# boadr.net
KiCad netlist of a schematic drawn in Altium Designer
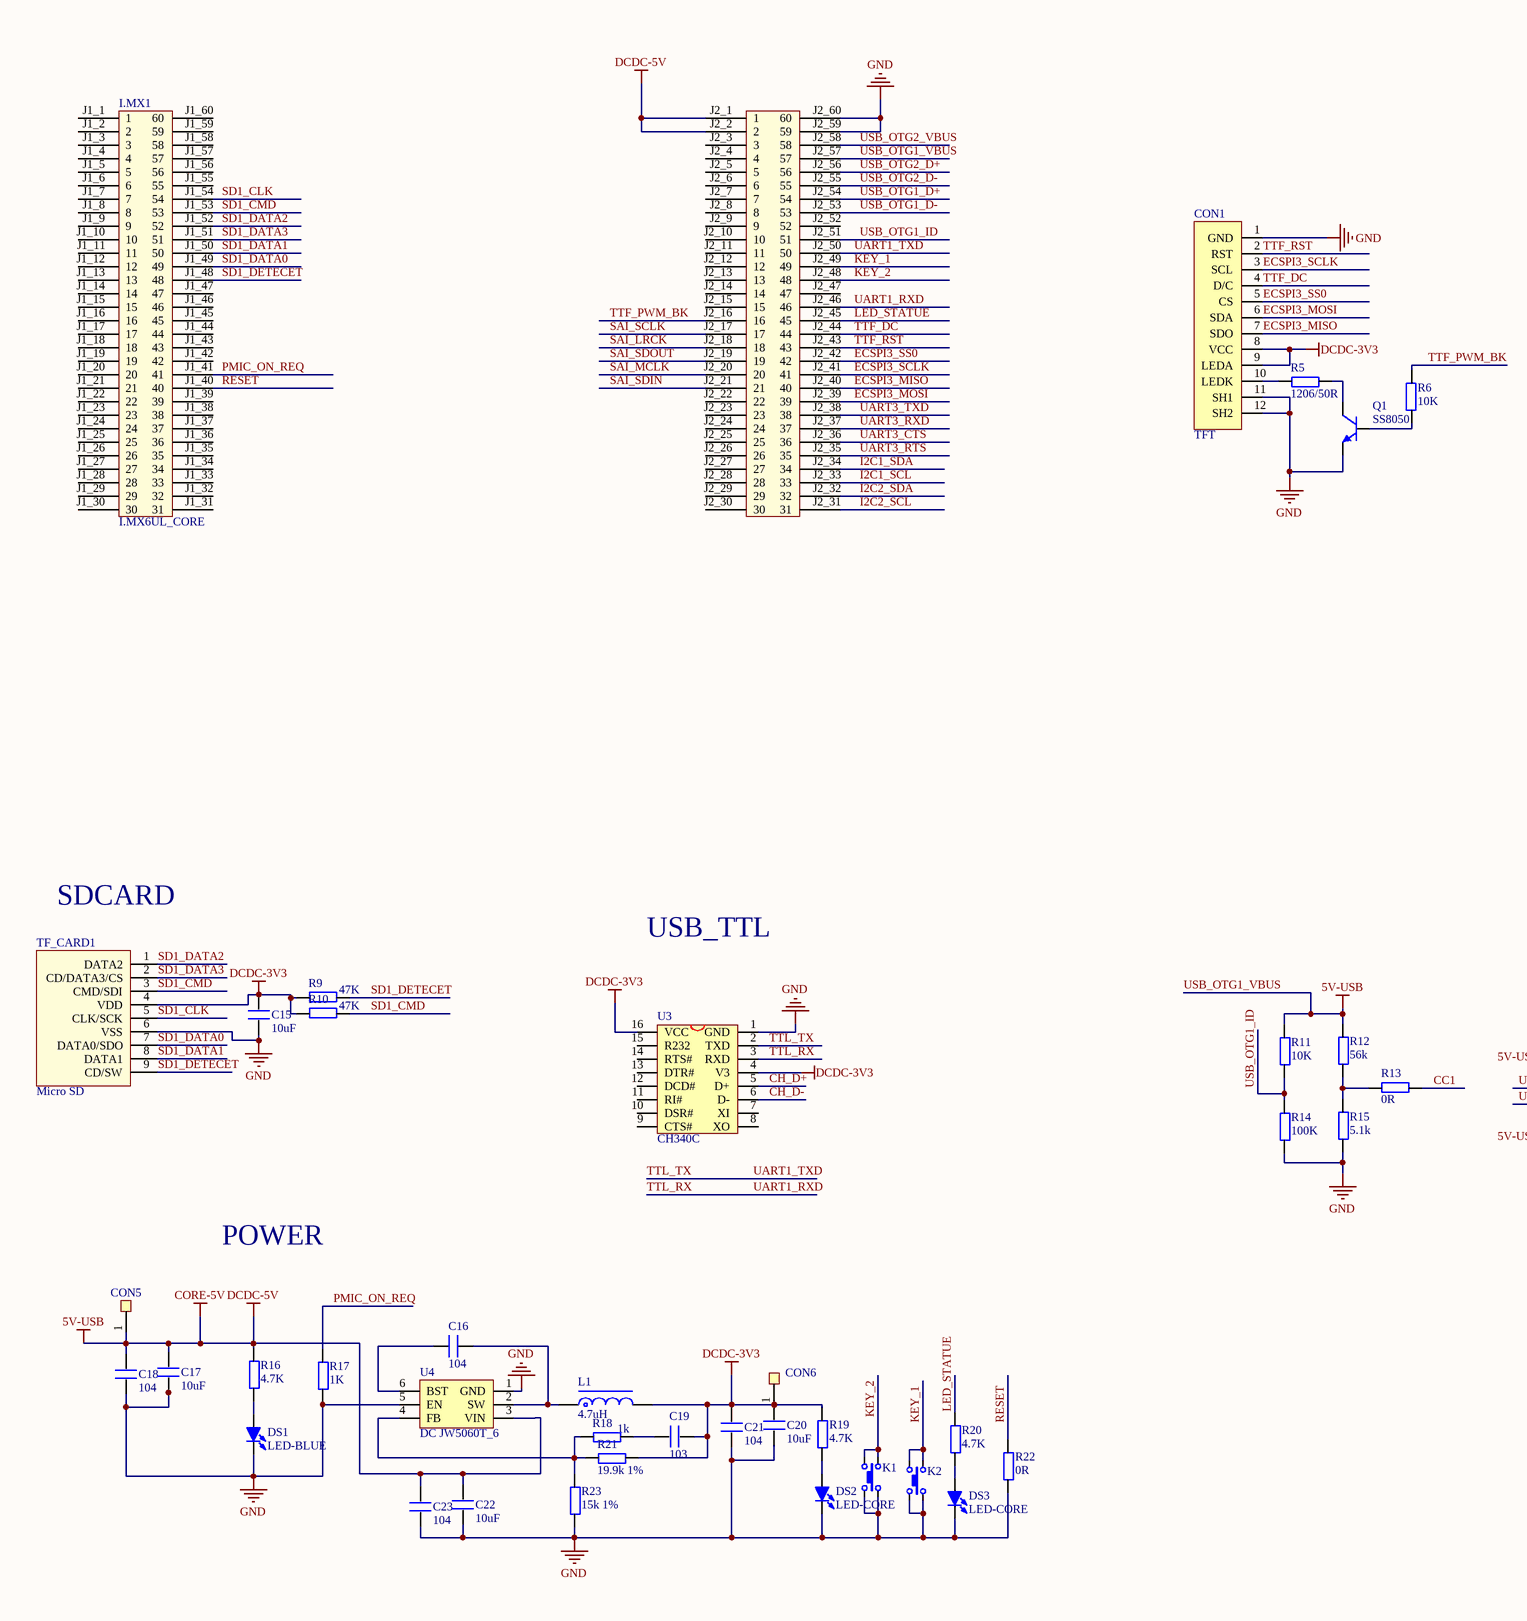
[diagram p0: boadr.SchDoc, left]
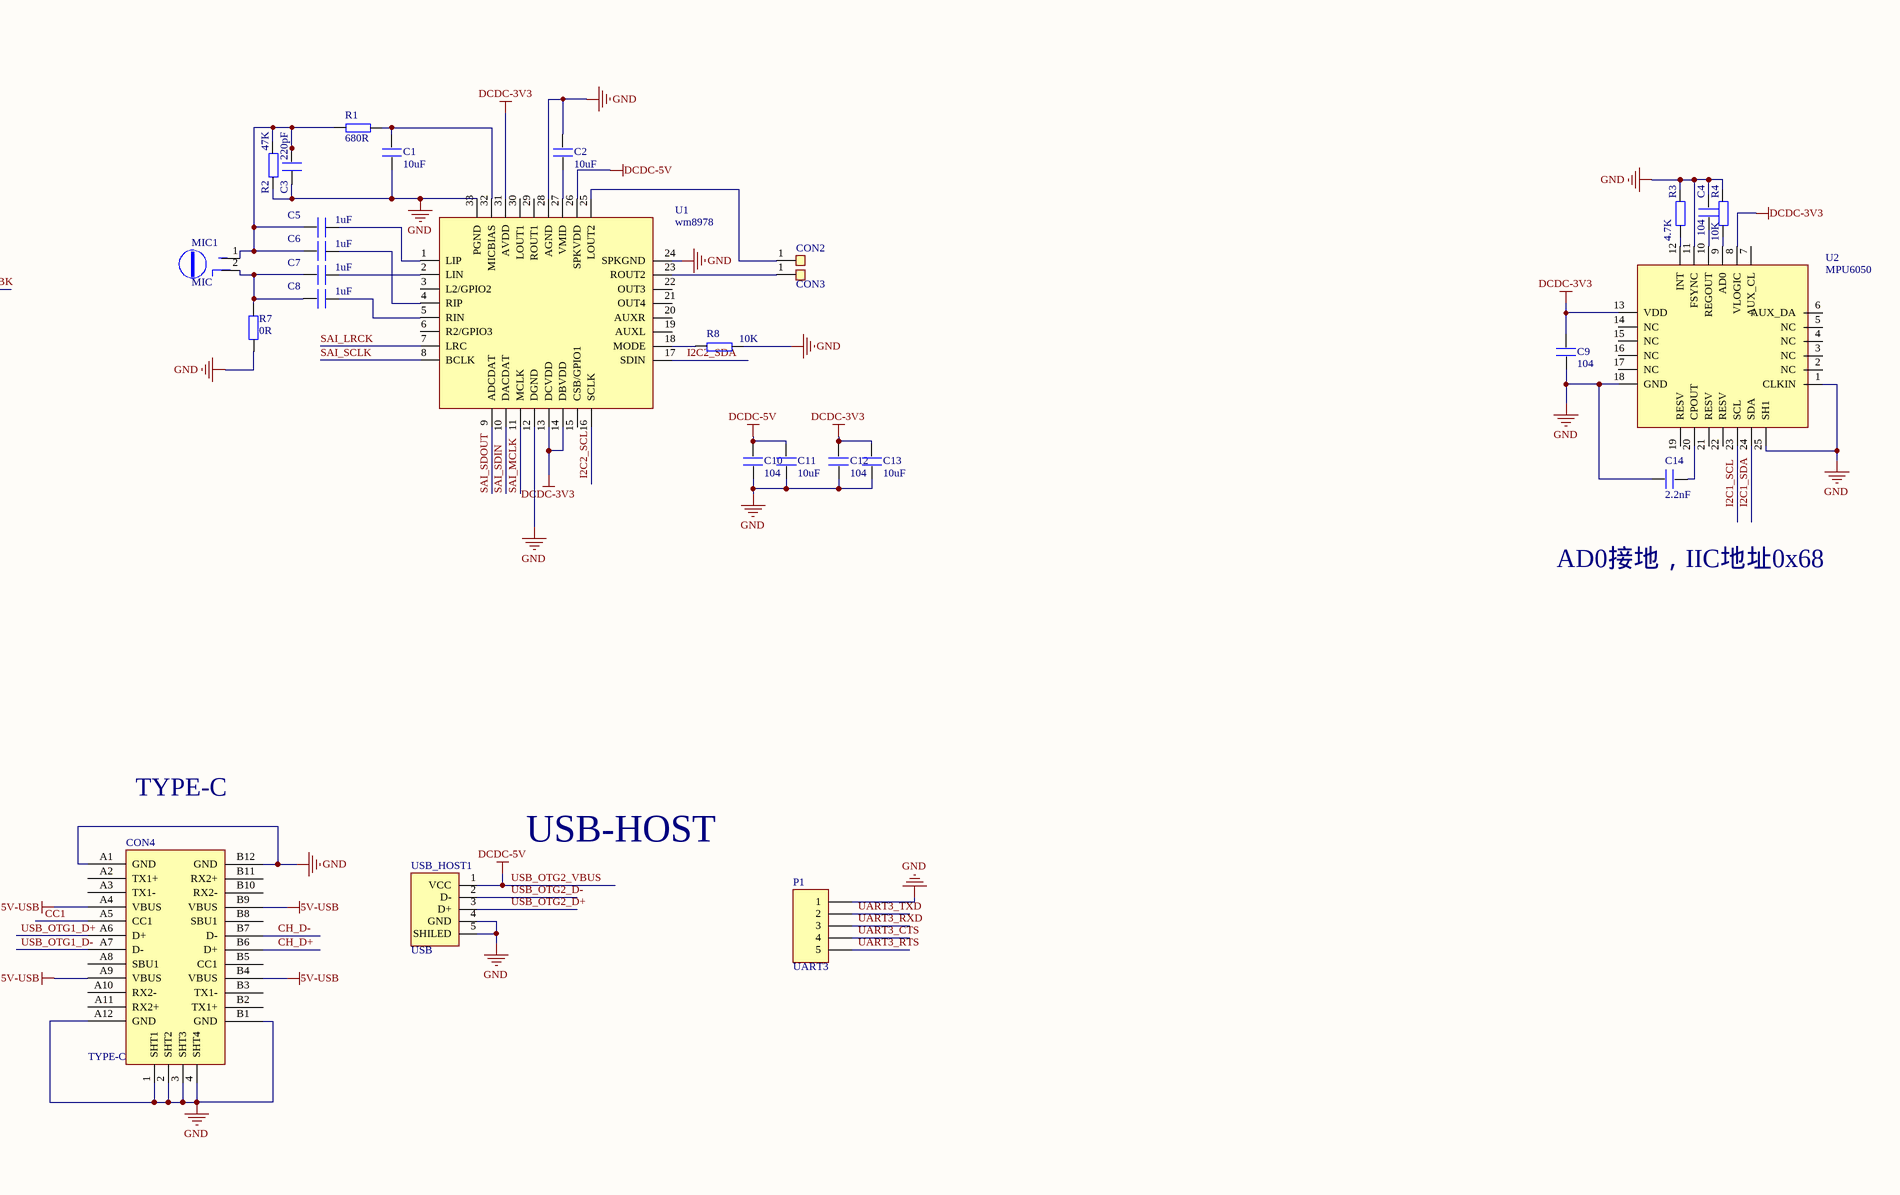
[diagram p1: boadr.SchDoc, right]

(export (version "E")
  (design (tool "Eeschema 10.0.6"))
  (components
    (comp (ref "C1") (value "10uF") (footprint "C 0603") (libsource (lib "IMX6UL_ALPHA(底板)_V2.0") (part "C")))
    (comp (ref "C2") (value "10uF") (footprint "C 0603") (libsource (lib "IMX6UL_ALPHA(底板)_V2.0") (part "C")))
    (comp (ref "C3")
      (value "220pF")
      (footprint "C 0603")
      (libsource (lib "IMX6UL_ALPHA(底板)_V2.0") (part "C"))
    )
    (comp (ref "C4") (value "104") (footprint "C 0603") (libsource (lib "IMX6UL_ALPHA(底板)_V2.0") (part "C")))
    (comp (ref "C5") (value "1uF") (footprint "C 0603") (libsource (lib "IMX6UL_ALPHA(底板)_V2.0") (part "C")))
    (comp (ref "C6") (value "1uF") (footprint "C 0603") (libsource (lib "IMX6UL_ALPHA(底板)_V2.0") (part "C")))
    (comp (ref "C7") (value "1uF") (footprint "C 0603") (libsource (lib "IMX6UL_ALPHA(底板)_V2.0") (part "C")))
    (comp (ref "C8") (value "1uF") (footprint "C 0603") (libsource (lib "IMX6UL_ALPHA(底板)_V2.0") (part "C")))
    (comp (ref "C9") (value "104") (footprint "C 0603") (libsource (lib "IMX6UL_ALPHA(底板)_V2.0") (part "C")))
    (comp (ref "C10") (value "104") (footprint "C 0603") (libsource (lib "IMX6UL_ALPHA(底板)_V2.0") (part "C")))
    (comp (ref "C11")
      (value "10uF")
      (footprint "C 0603")
      (libsource (lib "IMX6UL_ALPHA(底板)_V2.0") (part "C"))
    )
    (comp (ref "C12") (value "104") (footprint "C 0603") (libsource (lib "IMX6UL_ALPHA(底板)_V2.0") (part "C")))
    (comp (ref "C13")
      (value "10uF")
      (footprint "C 0603")
      (libsource (lib "IMX6UL_ALPHA(底板)_V2.0") (part "C"))
    )
    (comp (ref "C14")
      (value "2.2nF")
      (footprint "C 0603")
      (libsource (lib "IMX6UL_ALPHA(底板)_V2.0") (part "C"))
    )
    (comp (ref "C15")
      (value "10uF")
      (footprint "C 0603")
      (libsource (lib "IMX6UL_ALPHA(底板)_V2.0") (part "C"))
    )
    (comp (ref "C16") (value "104") (footprint "C 0603") (libsource (lib "IMX6UL_ALPHA(底板)_V2.0") (part "C")))
    (comp (ref "C17")
      (value "10uF")
      (footprint "C 0603")
      (libsource (lib "IMX6UL_ALPHA(底板)_V2.0") (part "C"))
    )
    (comp (ref "C18") (value "104") (footprint "C 0603") (libsource (lib "IMX6UL_ALPHA(底板)_V2.0") (part "C")))
    (comp (ref "C19") (value "103") (footprint "C 0603") (libsource (lib "IMX6UL_ALPHA(底板)_V2.0") (part "C")))
    (comp (ref "C20")
      (value "10uF")
      (footprint "C 0603")
      (libsource (lib "IMX6UL_ALPHA(底板)_V2.0") (part "C"))
    )
    (comp (ref "C21") (value "104") (footprint "C 0603") (libsource (lib "IMX6UL_ALPHA(底板)_V2.0") (part "C")))
    (comp (ref "C22")
      (value "10uF")
      (footprint "C 0603")
      (libsource (lib "IMX6UL_ALPHA(底板)_V2.0") (part "C"))
    )
    (comp (ref "C23") (value "104") (footprint "C 0603") (libsource (lib "IMX6UL_ALPHA(底板)_V2.0") (part "C")))
    (comp (ref "CON1")
      (value "TFT")
      (footprint "FPC连接器")
      (libsource (lib "Schlib_cloudy") (part "TFT_SPI_10PIN"))
    )
    (comp (ref "CON2") (value "connector") (footprint "PIN-1-TEST") (libsource (lib "") (part "PIN-1_1")))
    (comp (ref "CON3") (value "connector") (footprint "PIN-1-TEST") (libsource (lib "") (part "PIN-1_1")))
    (comp (ref "CON4")
      (value "TYPE-C")
      (footprint "type-c")
      (libsource (lib "Schlib_cloudy") (part "TYPE-C"))
    )
    (comp (ref "CON5")
      (value "connector")
      (footprint "PIN-1-TEST")
      (libsource (lib "Schlib_cloudy") (part "PIN-1"))
    )
    (comp (ref "CON6")
      (value "connector")
      (footprint "PIN-1-TEST")
      (libsource (lib "Schlib_cloudy") (part "PIN-1"))
    )
    (comp (ref "DS1")
      (value "LED-BLUE")
      (footprint "LED-0603")
      (description "贴片LED")
      (fields (field (name "版权归属") "源创客"))
      (libsource (lib "IMX6UL_ALPHA(底板)_V2.0") (part "LED-SMD"))
    )
    (comp (ref "DS2")
      (value "LED-CORE")
      (footprint "LED 0603R")
      (description "贴片LED")
      (fields (field (name "版权归属") "源创客"))
      (libsource (lib "IMX6UL_ALPHA(底板)_V2.0") (part "LED-SMD"))
    )
    (comp (ref "DS3")
      (value "LED-CORE")
      (footprint "LED 0603R")
      (description "贴片LED")
      (fields (field (name "版权归属") "源创客"))
      (libsource (lib "IMX6UL_ALPHA(底板)_V2.0") (part "LED-SMD"))
    )
    (comp (ref "I.MX1")
      (value "I.MX6UL_CORE")
      (footprint "I.MX6UL_CORE")
      (description "I.MX6UL核心板")
      (libsource (lib "IMX6UL_ALPHA(底板)_V2.0") (part "I.MX6UL核心板"))
    )
    (comp (ref "K1")
      (value "TACT 4P")
      (footprint "DS-THAM04-ABB-R")
      (description "Button")
      (libsource (lib "KitSprout") (part "ButtonTACT"))
    )
    (comp (ref "K2")
      (value "TACT 4P")
      (footprint "DS-THAM04-ABB-R")
      (description "Button")
      (libsource (lib "KitSprout") (part "ButtonTACT"))
    )
    (comp (ref "L1")
      (value "4.7uH")
      (footprint "L-SMD-0420")
      (description "功率屏蔽电感")
      (fields (field (name "版权归属") "源创客"))
      (libsource (lib "IMX6UL_ALPHA(底板)_V2.0") (part "L-CDRH"))
    )
    (comp (ref "MIC1")
      (value "MIC")
      (footprint "MIC-6022")
      (libsource (lib "IMX6UL_ALPHA(底板)_V2.0") (part "MIC"))
    )
    (comp (ref "P1")
      (value "UART3")
      (footprint "CON-1.27*5")
      (description "Header, 5-Pin")
      (fields (field (name "PUBLISHER") "Altium Limited"))
      (libsource (lib "Miscellaneous Connectors") (part "Header 5"))
    )
    (comp (ref "Q1")
      (value "SS8050")
      (footprint "SOT23-3N")
      (description "高频放大-NPN型")
      (fields (field (name "版权归属") "源创客"))
      (libsource (lib "IMX6UL_ALPHA(底板)_V2.0") (part "8050-SMD"))
    )
    (comp (ref "R1") (value "680R") (footprint "R 0603") (libsource (lib "IMX6UL_ALPHA(底板)_V2.0") (part "R")))
    (comp (ref "R2") (value "47K") (footprint "R 0603") (libsource (lib "IMX6UL_ALPHA(底板)_V2.0") (part "R")))
    (comp (ref "R3") (value "4.7K") (footprint "R 0603") (libsource (lib "IMX6UL_ALPHA(底板)_V2.0") (part "R")))
    (comp (ref "R4") (value "10K") (footprint "R 0603") (libsource (lib "IMX6UL_ALPHA(底板)_V2.0") (part "R")))
    (comp (ref "R5")
      (value "1206/50R")
      (footprint "0805")
      (libsource (lib "IMX6UL_ALPHA(底板)_V2.0") (part "R"))
    )
    (comp (ref "R6") (value "10K") (footprint "R 0603") (libsource (lib "IMX6UL_ALPHA(底板)_V2.0") (part "R")))
    (comp (ref "R7") (value "0R") (footprint "R 0603") (libsource (lib "IMX6UL_ALPHA(底板)_V2.0") (part "R")))
    (comp (ref "R8") (value "10K") (footprint "R 0603") (libsource (lib "IMX6UL_ALPHA(底板)_V2.0") (part "R")))
    (comp (ref "R9") (value "47K") (footprint "R 0603") (libsource (lib "IMX6UL_ALPHA(底板)_V2.0") (part "R")))
    (comp (ref "R10") (value "47K") (footprint "R 0603") (libsource (lib "IMX6UL_ALPHA(底板)_V2.0") (part "R")))
    (comp (ref "R11") (value "10K") (footprint "R 0603") (libsource (lib "IMX6UL_ALPHA(底板)_V2.0") (part "R")))
    (comp (ref "R12") (value "56k") (footprint "R 0603") (libsource (lib "IMX6UL_ALPHA(底板)_V2.0") (part "R")))
    (comp (ref "R13") (value "0R") (footprint "R 0603") (libsource (lib "IMX6UL_ALPHA(底板)_V2.0") (part "R")))
    (comp (ref "R14")
      (value "100K")
      (footprint "R 0603")
      (libsource (lib "IMX6UL_ALPHA(底板)_V2.0") (part "R"))
    )
    (comp (ref "R15")
      (value "5.1k")
      (footprint "R 0603")
      (libsource (lib "IMX6UL_ALPHA(底板)_V2.0") (part "R"))
    )
    (comp (ref "R16")
      (value "4.7K")
      (footprint "R 0603")
      (libsource (lib "IMX6UL_ALPHA(底板)_V2.0") (part "R"))
    )
    (comp (ref "R17") (value "1K") (footprint "R 0603") (libsource (lib "IMX6UL_ALPHA(底板)_V2.0") (part "R")))
    (comp (ref "R18") (value "1k") (footprint "R 0603") (libsource (lib "IMX6UL_ALPHA(底板)_V2.0") (part "R")))
    (comp (ref "R19")
      (value "4.7K")
      (footprint "R 0603")
      (libsource (lib "IMX6UL_ALPHA(底板)_V2.0") (part "R"))
    )
    (comp (ref "R20")
      (value "4.7K")
      (footprint "R 0603")
      (libsource (lib "IMX6UL_ALPHA(底板)_V2.0") (part "R"))
    )
    (comp (ref "R21")
      (value "19.9k 1%")
      (footprint "R 0603")
      (libsource (lib "IMX6UL_ALPHA(底板)_V2.0") (part "R"))
    )
    (comp (ref "R22") (value "0R") (footprint "R 0603") (libsource (lib "IMX6UL_ALPHA(底板)_V2.0") (part "R")))
    (comp (ref "R23")
      (value "15k 1%")
      (footprint "R 0603")
      (libsource (lib "IMX6UL_ALPHA(底板)_V2.0") (part "R"))
    )
    (comp (ref "TF_CARD1")
      (value "Micro SD")
      (footprint "Micro SD")
      (description "Micro SD卡")
      (fields (field (name "版权归属") "源创客"))
      (libsource (lib "IMX6UL_ALPHA(底板)_V2.0") (part "Micro SD"))
    )
    (comp (ref "U1")
      (value "wm8978")
      (footprint "QFN50P500X500X80_HS-33N")
      (description "音频")
      (libsource (lib "Schlib_cloudy") (part "wm8978"))
    )
    (comp (ref "U2")
      (value "MPU6050")
      (footprint "QFN50P400X400X90_HS-25N")
      (libsource (lib "Schlib_cloudy") (part "MPU6050"))
    )
    (comp (ref "U3")
      (value "CH340C")
      (footprint "SOP16_N")
      (description "USB2UART")
      (libsource (lib "IMX6UL_ALPHA(底板)_V2.0") (part "CH340G"))
    )
    (comp (ref "U4")
      (value "DC JW5060T_6")
      (footprint "SOT23-6N")
      (description "DC降压芯片")
      (libsource (lib "IMX6UL_ALPHA(底板)_V2.0") (part "DC JW5060T_6"))
    )
    (comp (ref "USB_HOST1")
      (value "USB")
      (footprint "USB-A/S_C")
      (description "USB-A型母接口")
      (fields (field (name "版权归属") "源创客"))
      (libsource (lib "IMX6UL_ALPHA(底板)_V2.0") (part "USB-A/S"))
    )
  )
  (nets
    (net (code "1") (name "/CC1") (class "Default")
      (node (ref "CON4") (pin "A5") (pinfunction "CC1_A5") (pintype "passive"))
      (node (ref "R13") (pin "1") (pintype "passive"))
    )
    (net (code "2") (name "/CH_D+") (class "Default")
      (node (ref "CON4") (pin "B6") (pinfunction "D+_B6") (pintype "passive"))
      (node (ref "U3") (pin "5") (pinfunction "D+_5") (pintype "passive"))
    )
    (net (code "3") (name "/CH_D-") (class "Default")
      (node (ref "CON4") (pin "B7") (pinfunction "D-_B7") (pintype "passive"))
      (node (ref "U3") (pin "6") (pinfunction "D-_6") (pintype "passive"))
    )
    (net (code "4") (name "/ECSPI3_MISO") (class "Default")
      (node (ref "CON1") (pin "7") (pinfunction "SDO_7") (pintype "passive"))
      (node (ref "I.MX1") (pin "J2_40") (pinfunction "40_J2_40") (pintype "passive"))
    )
    (net (code "5") (name "/ECSPI3_MOSI") (class "Default")
      (node (ref "CON1") (pin "6") (pinfunction "SDA_6") (pintype "passive"))
      (node (ref "I.MX1") (pin "J2_39") (pinfunction "39_J2_39") (pintype "passive"))
    )
    (net (code "6") (name "/ECSPI3_SCLK") (class "Default")
      (node (ref "CON1") (pin "3") (pinfunction "SCL_3") (pintype "passive"))
      (node (ref "I.MX1") (pin "J2_41") (pinfunction "41_J2_41") (pintype "passive"))
    )
    (net (code "7") (name "/ECSPI3_SS0") (class "Default")
      (node (ref "CON1") (pin "5") (pinfunction "CS_5") (pintype "passive"))
      (node (ref "I.MX1") (pin "J2_42") (pinfunction "42_J2_42") (pintype "passive"))
    )
    (net (code "8") (name "/I2C1_SCL") (class "Default")
      (node (ref "I.MX1") (pin "J2_33") (pinfunction "33_J2_33") (pintype "passive"))
      (node (ref "U2") (pin "23") (pinfunction "SCL_23") (pintype "passive"))
    )
    (net (code "9") (name "/I2C1_SDA") (class "Default")
      (node (ref "I.MX1") (pin "J2_34") (pinfunction "34_J2_34") (pintype "passive"))
      (node (ref "U2") (pin "24") (pinfunction "SDA_24") (pintype "passive"))
    )
    (net (code "10") (name "/I2C2_SCL") (class "Default")
      (node (ref "I.MX1") (pin "J2_31") (pinfunction "31_J2_31") (pintype "passive"))
      (node (ref "U1") (pin "16") (pinfunction "SCLK_16") (pintype "passive"))
    )
    (net (code "11") (name "/I2C2_SDA") (class "Default")
      (node (ref "I.MX1") (pin "J2_32") (pinfunction "32_J2_32") (pintype "passive"))
      (node (ref "U1") (pin "17") (pinfunction "SDIN_17") (pintype "passive"))
    )
    (net (code "12") (name "/KEY_1") (class "Default")
      (node (ref "I.MX1") (pin "J2_49") (pinfunction "49_J2_49") (pintype "passive"))
      (node (ref "K2") (pin "2") (pinfunction "2_2") (pintype "passive"))
      (node (ref "K2") (pin "4") (pinfunction "4_4") (pintype "passive"))
    )
    (net (code "13") (name "/KEY_2") (class "Default")
      (node (ref "I.MX1") (pin "J2_48") (pinfunction "48_J2_48") (pintype "passive"))
      (node (ref "K1") (pin "2") (pinfunction "2_2") (pintype "passive"))
      (node (ref "K1") (pin "4") (pinfunction "4_4") (pintype "passive"))
    )
    (net (code "14") (name "/LED_STATUE") (class "Default")
      (node (ref "I.MX1") (pin "J2_45") (pinfunction "45_J2_45") (pintype "passive"))
      (node (ref "R20") (pin "2") (pintype "passive"))
    )
    (net (code "15") (name "/PMIC_ON_REQ") (class "Default")
      (node (ref "I.MX1") (pin "J1_41") (pinfunction "41_J1_41") (pintype "passive"))
      (node (ref "R17") (pin "2") (pintype "passive"))
    )
    (net (code "16") (name "/RESET") (class "Default")
      (node (ref "I.MX1") (pin "J1_40") (pinfunction "40_J1_40") (pintype "passive"))
      (node (ref "R22") (pin "2") (pintype "passive"))
    )
    (net (code "17") (name "/SAI_LRCK") (class "Default")
      (node (ref "I.MX1") (pin "J2_18") (pinfunction "18_J2_18") (pintype "passive"))
      (node (ref "U1") (pin "7") (pinfunction "LRC_7") (pintype "passive"))
    )
    (net (code "18") (name "/SAI_MCLK") (class "Default")
      (node (ref "I.MX1") (pin "J2_20") (pinfunction "20_J2_20") (pintype "passive"))
      (node (ref "U1") (pin "11") (pinfunction "MCLK_11") (pintype "passive"))
    )
    (net (code "19") (name "/SAI_SCLK") (class "Default")
      (node (ref "I.MX1") (pin "J2_17") (pinfunction "17_J2_17") (pintype "passive"))
      (node (ref "U1") (pin "8") (pinfunction "BCLK_8") (pintype "passive"))
    )
    (net (code "20") (name "/SAI_SDIN") (class "Default")
      (node (ref "I.MX1") (pin "J2_21") (pinfunction "21_J2_21") (pintype "passive"))
      (node (ref "U1") (pin "10") (pinfunction "DACDAT_10") (pintype "passive"))
    )
    (net (code "21") (name "/SAI_SDOUT") (class "Default")
      (node (ref "I.MX1") (pin "J2_19") (pinfunction "19_J2_19") (pintype "passive"))
      (node (ref "U1") (pin "9") (pinfunction "ADCDAT_9") (pintype "passive"))
    )
    (net (code "22") (name "/SD1_CLK") (class "Default")
      (node (ref "I.MX1") (pin "J1_54") (pinfunction "54_J1_54") (pintype "passive"))
      (node (ref "TF_CARD1") (pin "5") (pinfunction "CLK/SCK_5") (pintype "passive"))
    )
    (net (code "23") (name "/SD1_CMD") (class "Default")
      (node (ref "I.MX1") (pin "J1_53") (pinfunction "53_J1_53") (pintype "passive"))
      (node (ref "R10") (pin "1") (pintype "passive"))
      (node (ref "TF_CARD1") (pin "3") (pinfunction "CMD/SDI_3") (pintype "passive"))
    )
    (net (code "24") (name "/SD1_DATA0") (class "Default")
      (node (ref "I.MX1") (pin "J1_49") (pinfunction "49_J1_49") (pintype "passive"))
      (node (ref "TF_CARD1") (pin "7") (pinfunction "DATA0/SDO_7") (pintype "passive"))
    )
    (net (code "25") (name "/SD1_DATA1") (class "Default")
      (node (ref "I.MX1") (pin "J1_50") (pinfunction "50_J1_50") (pintype "passive"))
      (node (ref "TF_CARD1") (pin "8") (pinfunction "DATA1_8") (pintype "passive"))
    )
    (net (code "26") (name "/SD1_DATA2") (class "Default")
      (node (ref "I.MX1") (pin "J1_52") (pinfunction "52_J1_52") (pintype "passive"))
      (node (ref "TF_CARD1") (pin "1") (pinfunction "DATA2_1") (pintype "passive"))
    )
    (net (code "27") (name "/SD1_DATA3") (class "Default")
      (node (ref "I.MX1") (pin "J1_51") (pinfunction "51_J1_51") (pintype "passive"))
      (node (ref "TF_CARD1") (pin "2") (pinfunction "CD/DATA3/CS_2") (pintype "passive"))
    )
    (net (code "28") (name "/SD1_DETECET") (class "Default")
      (node (ref "I.MX1") (pin "J1_48") (pinfunction "48_J1_48") (pintype "passive"))
      (node (ref "R9") (pin "1") (pintype "passive"))
      (node (ref "TF_CARD1") (pin "9") (pinfunction "CD/SW_9") (pintype "passive"))
    )
    (net (code "29") (name "/TTF_DC") (class "Default")
      (node (ref "CON1") (pin "4") (pinfunction "D/C_4") (pintype "passive"))
      (node (ref "I.MX1") (pin "J2_44") (pinfunction "44_J2_44") (pintype "passive"))
    )
    (net (code "30") (name "/TTF_PWM_BK") (class "Default")
      (node (ref "I.MX1") (pin "J2_16") (pinfunction "16_J2_16") (pintype "passive"))
      (node (ref "R6") (pin "1") (pintype "passive"))
    )
    (net (code "31") (name "/TTF_RST") (class "Default")
      (node (ref "CON1") (pin "2") (pinfunction "RST_2") (pintype "passive"))
      (node (ref "I.MX1") (pin "J2_43") (pinfunction "43_J2_43") (pintype "passive"))
    )
    (net (code "32") (name "/TTL_RX") (class "Default")
      (node (ref "I.MX1") (pin "J2_46") (pinfunction "46_J2_46") (pintype "passive"))
      (node (ref "U3") (pin "3") (pinfunction "RXD_3") (pintype "passive"))
    )
    (net (code "33") (name "/TTL_TX") (class "Default")
      (node (ref "I.MX1") (pin "J2_50") (pinfunction "50_J2_50") (pintype "passive"))
      (node (ref "U3") (pin "2") (pinfunction "TXD_2") (pintype "passive"))
    )
    (net (code "34") (name "/UART3_CTS") (class "Default")
      (node (ref "I.MX1") (pin "J2_36") (pinfunction "36_J2_36") (pintype "passive"))
      (node (ref "P1") (pin "4") (pinfunction "4_4") (pintype "passive"))
    )
    (net (code "35") (name "/UART3_RTS") (class "Default")
      (node (ref "I.MX1") (pin "J2_35") (pinfunction "35_J2_35") (pintype "passive"))
      (node (ref "P1") (pin "5") (pinfunction "5_5") (pintype "passive"))
    )
    (net (code "36") (name "/UART3_RXD") (class "Default")
      (node (ref "I.MX1") (pin "J2_37") (pinfunction "37_J2_37") (pintype "passive"))
      (node (ref "P1") (pin "3") (pinfunction "3_3") (pintype "passive"))
    )
    (net (code "37") (name "/UART3_TXD") (class "Default")
      (node (ref "I.MX1") (pin "J2_38") (pinfunction "38_J2_38") (pintype "passive"))
      (node (ref "P1") (pin "2") (pinfunction "2_2") (pintype "passive"))
    )
    (net (code "38") (name "/USB_OTG1_D+") (class "Default")
      (node (ref "CON4") (pin "A6") (pinfunction "D+_A6") (pintype "passive"))
      (node (ref "I.MX1") (pin "J2_54") (pinfunction "54_J2_54") (pintype "passive"))
    )
    (net (code "39") (name "/USB_OTG1_D-") (class "Default")
      (node (ref "CON4") (pin "A7") (pinfunction "D-_A7") (pintype "passive"))
      (node (ref "I.MX1") (pin "J2_53") (pinfunction "53_J2_53") (pintype "passive"))
    )
    (net (code "40") (name "/USB_OTG1_ID") (class "Default")
      (node (ref "I.MX1") (pin "J2_51") (pinfunction "51_J2_51") (pintype "passive"))
      (node (ref "R11") (pin "1") (pintype "passive"))
      (node (ref "R14") (pin "2") (pintype "passive"))
    )
    (net (code "41") (name "/USB_OTG2_D+") (class "Default")
      (node (ref "I.MX1") (pin "J2_56") (pinfunction "56_J2_56") (pintype "passive"))
      (node (ref "USB_HOST1") (pin "3") (pinfunction "D+_3") (pintype "passive"))
    )
    (net (code "42") (name "/USB_OTG2_D-") (class "Default")
      (node (ref "I.MX1") (pin "J2_55") (pinfunction "55_J2_55") (pintype "passive"))
      (node (ref "USB_HOST1") (pin "2") (pinfunction "D-_2") (pintype "passive"))
    )
    (net (code "43") (name "5V-USB") (class "Default")
      (node (ref "C10") (pin "1") (pintype "passive"))
      (node (ref "C11") (pin "1") (pintype "passive"))
      (node (ref "C17") (pin "2") (pintype "passive"))
      (node (ref "C18") (pin "2") (pintype "passive"))
      (node (ref "C22") (pin "2") (pintype "passive"))
      (node (ref "C23") (pin "2") (pintype "passive"))
      (node (ref "CON4") (pin "A4") (pinfunction "VBUS_A4") (pintype "passive"))
      (node (ref "CON4") (pin "A9") (pinfunction "VBUS_A9") (pintype "passive"))
      (node (ref "CON4") (pin "B4") (pinfunction "VBUS_B4") (pintype "passive"))
      (node (ref "CON4") (pin "B9") (pinfunction "VBUS_B9") (pintype "passive"))
      (node (ref "CON5") (pin "1") (pinfunction "1_1") (pintype "passive"))
      (node (ref "I.MX1") (pin "J2_1") (pinfunction "1_J2_1") (pintype "passive"))
      (node (ref "I.MX1") (pin "J2_2") (pinfunction "2_J2_2") (pintype "passive"))
      (node (ref "I.MX1") (pin "J2_57") (pinfunction "57_J2_57") (pintype "passive"))
      (node (ref "I.MX1") (pin "J2_58") (pinfunction "58_J2_58") (pintype "passive"))
      (node (ref "R11") (pin "2") (pintype "passive"))
      (node (ref "R12") (pin "2") (pintype "passive"))
      (node (ref "R16") (pin "2") (pintype "passive"))
      (node (ref "U1") (pin "26") (pinfunction "SPKVDD_26") (pintype "passive"))
      (node (ref "U4") (pin "3") (pinfunction "VIN_3") (pintype "passive"))
      (node (ref "USB_HOST1") (pin "1") (pinfunction "VCC_1") (pintype "passive"))
    )
    (net (code "44") (name "DCDC-3V3") (class "Default")
      (node (ref "C12") (pin "1") (pintype "passive"))
      (node (ref "C13") (pin "1") (pintype "passive"))
      (node (ref "C15") (pin "2") (pintype "passive"))
      (node (ref "C19") (pin "1") (pintype "passive"))
      (node (ref "C20") (pin "2") (pintype "passive"))
      (node (ref "C21") (pin "2") (pintype "passive"))
      (node (ref "C9") (pin "1") (pintype "passive"))
      (node (ref "CON1") (pin "8") (pinfunction "VCC_8") (pintype "passive"))
      (node (ref "CON1") (pin "9") (pinfunction "LEDA_9") (pintype "passive"))
      (node (ref "CON6") (pin "1") (pinfunction "1_1") (pintype "passive"))
      (node (ref "L1") (pin "2") (pinfunction "2_2") (pintype "passive"))
      (node (ref "R10") (pin "2") (pintype "passive"))
      (node (ref "R19") (pin "2") (pintype "passive"))
      (node (ref "R21") (pin "2") (pintype "passive"))
      (node (ref "R9") (pin "2") (pintype "passive"))
      (node (ref "TF_CARD1") (pin "4") (pinfunction "VDD_4") (pintype "passive"))
      (node (ref "U1") (pin "13") (pinfunction "DCVDD_13") (pintype "passive"))
      (node (ref "U1") (pin "14") (pinfunction "DBVDD_14") (pintype "passive"))
      (node (ref "U1") (pin "31") (pinfunction "AVDD_31") (pintype "passive"))
      (node (ref "U2") (pin "13") (pinfunction "VDD_13") (pintype "passive"))
      (node (ref "U2") (pin "8") (pinfunction "VLOGIC_8") (pintype "passive"))
      (node (ref "U3") (pin "16") (pinfunction "VCC_16") (pintype "passive"))
      (node (ref "U3") (pin "4") (pinfunction "V3_4") (pintype "passive"))
    )
    (net (code "45") (name "GND") (class "Default")
      (node (ref "C1") (pin "2") (pintype "passive"))
      (node (ref "C10") (pin "2") (pintype "passive"))
      (node (ref "C11") (pin "2") (pintype "passive"))
      (node (ref "C12") (pin "2") (pintype "passive"))
      (node (ref "C13") (pin "2") (pintype "passive"))
      (node (ref "C14") (pin "1") (pintype "passive"))
      (node (ref "C15") (pin "1") (pintype "passive"))
      (node (ref "C17") (pin "1") (pintype "passive"))
      (node (ref "C18") (pin "1") (pintype "passive"))
      (node (ref "C2") (pin "1") (pintype "passive"))
      (node (ref "C20") (pin "1") (pintype "passive"))
      (node (ref "C21") (pin "1") (pintype "passive"))
      (node (ref "C22") (pin "1") (pintype "passive"))
      (node (ref "C23") (pin "1") (pintype "passive"))
      (node (ref "C3") (pin "2") (pintype "passive"))
      (node (ref "C4") (pin "1") (pintype "passive"))
      (node (ref "C9") (pin "2") (pintype "passive"))
      (node (ref "CON1") (pin "1") (pinfunction "GND_1") (pintype "passive"))
      (node (ref "CON1") (pin "11") (pinfunction "SH1_11") (pintype "passive"))
      (node (ref "CON1") (pin "12") (pinfunction "SH2_12") (pintype "passive"))
      (node (ref "CON4") (pin "1") (pinfunction "SHT1_1") (pintype "passive"))
      (node (ref "CON4") (pin "2") (pinfunction "SHT2_2") (pintype "passive"))
      (node (ref "CON4") (pin "3") (pinfunction "SHT3_3") (pintype "passive"))
      (node (ref "CON4") (pin "4") (pinfunction "SHT4_4") (pintype "passive"))
      (node (ref "CON4") (pin "A1") (pinfunction "GND_A1") (pintype "passive"))
      (node (ref "CON4") (pin "A12") (pinfunction "GND_A12") (pintype "passive"))
      (node (ref "CON4") (pin "B1") (pinfunction "GND_B1") (pintype "passive"))
      (node (ref "CON4") (pin "B12") (pinfunction "GND_B12") (pintype "passive"))
      (node (ref "DS1") (pin "2") (pinfunction "K_2") (pintype "passive"))
      (node (ref "DS2") (pin "2") (pinfunction "K_2") (pintype "passive"))
      (node (ref "DS3") (pin "2") (pinfunction "K_2") (pintype "passive"))
      (node (ref "I.MX1") (pin "J2_59") (pinfunction "59_J2_59") (pintype "passive"))
      (node (ref "I.MX1") (pin "J2_60") (pinfunction "60_J2_60") (pintype "passive"))
      (node (ref "K1") (pin "1") (pinfunction "1_1") (pintype "passive"))
      (node (ref "K1") (pin "3") (pinfunction "3_3") (pintype "passive"))
      (node (ref "K2") (pin "1") (pinfunction "1_1") (pintype "passive"))
      (node (ref "K2") (pin "3") (pinfunction "3_3") (pintype "passive"))
      (node (ref "P1") (pin "1") (pinfunction "1_1") (pintype "passive"))
      (node (ref "Q1") (pin "2") (pinfunction "E_2") (pintype "passive"))
      (node (ref "R14") (pin "1") (pintype "passive"))
      (node (ref "R15") (pin "1") (pintype "passive"))
      (node (ref "R17") (pin "1") (pintype "passive"))
      (node (ref "R2") (pin "1") (pintype "passive"))
      (node (ref "R22") (pin "1") (pintype "passive"))
      (node (ref "R23") (pin "1") (pintype "passive"))
      (node (ref "R3") (pin "2") (pintype "passive"))
      (node (ref "R4") (pin "2") (pintype "passive"))
      (node (ref "R7") (pin "2") (pintype "passive"))
      (node (ref "R8") (pin "2") (pintype "passive"))
      (node (ref "TF_CARD1") (pin "6") (pinfunction "VSS_6") (pintype "passive"))
      (node (ref "U1") (pin "12") (pinfunction "DGND_12") (pintype "passive"))
      (node (ref "U1") (pin "24") (pinfunction "SPKGND_24") (pintype "passive"))
      (node (ref "U1") (pin "28") (pinfunction "AGND_28") (pintype "passive"))
      (node (ref "U1") (pin "33") (pinfunction "PGND_33") (pintype "passive"))
      (node (ref "U2") (pin "1") (pinfunction "CLKIN_1") (pintype "passive"))
      (node (ref "U2") (pin "11") (pinfunction "FSYNC_11") (pintype "passive"))
      (node (ref "U2") (pin "18") (pinfunction "GND_18") (pintype "passive"))
      (node (ref "U2") (pin "25") (pinfunction "SH1_25") (pintype "passive"))
      (node (ref "U3") (pin "1") (pinfunction "GND_1") (pintype "passive"))
      (node (ref "U4") (pin "1") (pinfunction "GND_1") (pintype "passive"))
      (node (ref "U4") (pin "5") (pinfunction "EN_5") (pintype "passive"))
      (node (ref "USB_HOST1") (pin "4") (pinfunction "GND_4") (pintype "passive"))
      (node (ref "USB_HOST1") (pin "5") (pinfunction "SHILED_5") (pintype "passive"))
    )
    (net (code "46") (name "Net-(C19-Pad2)") (class "Default")
      (node (ref "C19") (pin "2") (pintype "passive"))
      (node (ref "R18") (pin "2") (pintype "passive"))
    )
    (net (code "47") (name "Net-(CON1-LEDK)") (class "Default")
      (node (ref "CON1") (pin "10") (pinfunction "LEDK_10") (pintype "passive"))
      (node (ref "R5") (pin "1") (pintype "passive"))
    )
    (net (code "48") (name "Net-(DS1-A)") (class "Default")
      (node (ref "DS1") (pin "1") (pinfunction "A_1") (pintype "passive"))
      (node (ref "R16") (pin "1") (pintype "passive"))
    )
    (net (code "49") (name "Net-(DS2-A)") (class "Default")
      (node (ref "DS2") (pin "1") (pinfunction "A_1") (pintype "passive"))
      (node (ref "R19") (pin "1") (pintype "passive"))
    )
    (net (code "50") (name "Net-(DS3-A)") (class "Default")
      (node (ref "DS3") (pin "1") (pinfunction "A_1") (pintype "passive"))
      (node (ref "R20") (pin "1") (pintype "passive"))
    )
    (net (code "51") (name "Net-(MIC1-GND)") (class "Default")
      (node (ref "C7") (pin "2") (pintype "passive"))
      (node (ref "C8") (pin "2") (pintype "passive"))
      (node (ref "MIC1") (pin "2") (pinfunction "GND_2") (pintype "passive"))
      (node (ref "R7") (pin "1") (pintype "passive"))
    )
    (net (code "52") (name "Net-(MIC1-VCC)") (class "Default")
      (node (ref "C3") (pin "1") (pintype "passive"))
      (node (ref "C5") (pin "2") (pintype "passive"))
      (node (ref "C6") (pin "2") (pintype "passive"))
      (node (ref "MIC1") (pin "1") (pinfunction "VCC_1") (pintype "passive"))
      (node (ref "R1") (pin "1") (pintype "passive"))
      (node (ref "R2") (pin "2") (pintype "passive"))
    )
    (net (code "53") (name "Net-(Q1-B)") (class "Default")
      (node (ref "Q1") (pin "1") (pinfunction "B_1") (pintype "passive"))
      (node (ref "R6") (pin "2") (pintype "passive"))
    )
    (net (code "54") (name "Net-(Q1-C)") (class "Default")
      (node (ref "Q1") (pin "3") (pinfunction "C_3") (pintype "passive"))
      (node (ref "R5") (pin "2") (pintype "passive"))
    )
    (net (code "55") (name "Net-(R12-Pad1)") (class "Default")
      (node (ref "R12") (pin "1") (pintype "passive"))
      (node (ref "R13") (pin "2") (pintype "passive"))
      (node (ref "R15") (pin "2") (pintype "passive"))
    )
    (net (code "56") (name "Net-(U1-LIN)") (class "Default")
      (node (ref "C7") (pin "1") (pintype "passive"))
      (node (ref "U1") (pin "2") (pinfunction "LIN_2") (pintype "passive"))
    )
    (net (code "57") (name "Net-(U1-LIP)") (class "Default")
      (node (ref "C5") (pin "1") (pintype "passive"))
      (node (ref "U1") (pin "1") (pinfunction "LIP_1") (pintype "passive"))
    )
    (net (code "58") (name "Net-(U1-LOUT2)") (class "Default")
      (node (ref "CON2") (pin "1") (pinfunction "1_1") (pintype "passive"))
      (node (ref "U1") (pin "25") (pinfunction "LOUT2_25") (pintype "passive"))
    )
    (net (code "59") (name "Net-(U1-MICBIAS)") (class "Default")
      (node (ref "C1") (pin "1") (pintype "passive"))
      (node (ref "R1") (pin "2") (pintype "passive"))
      (node (ref "U1") (pin "32") (pinfunction "MICBIAS_32") (pintype "passive"))
    )
    (net (code "60") (name "Net-(U1-MODE)") (class "Default")
      (node (ref "R8") (pin "1") (pintype "passive"))
      (node (ref "U1") (pin "18") (pinfunction "MODE_18") (pintype "passive"))
    )
    (net (code "61") (name "Net-(U1-RIN)") (class "Default")
      (node (ref "C8") (pin "1") (pintype "passive"))
      (node (ref "U1") (pin "5") (pinfunction "RIN_5") (pintype "passive"))
    )
    (net (code "62") (name "Net-(U1-RIP)") (class "Default")
      (node (ref "C6") (pin "1") (pintype "passive"))
      (node (ref "U1") (pin "4") (pinfunction "RIP_4") (pintype "passive"))
    )
    (net (code "63") (name "Net-(U1-ROUT2)") (class "Default")
      (node (ref "CON3") (pin "1") (pinfunction "1_1") (pintype "passive"))
      (node (ref "U1") (pin "23") (pinfunction "ROUT2_23") (pintype "passive"))
    )
    (net (code "64") (name "Net-(U1-VMID)") (class "Default")
      (node (ref "C2") (pin "2") (pintype "passive"))
      (node (ref "U1") (pin "27") (pinfunction "VMID_27") (pintype "passive"))
    )
    (net (code "65") (name "Net-(U2-AD0)") (class "Default")
      (node (ref "R4") (pin "1") (pintype "passive"))
      (node (ref "U2") (pin "9") (pinfunction "AD0_9") (pintype "passive"))
    )
    (net (code "66") (name "Net-(U2-CPOUT)") (class "Default")
      (node (ref "C14") (pin "2") (pintype "passive"))
      (node (ref "U2") (pin "20") (pinfunction "CPOUT_20") (pintype "passive"))
    )
    (net (code "67") (name "Net-(U2-INT)") (class "Default")
      (node (ref "R3") (pin "1") (pintype "passive"))
      (node (ref "U2") (pin "12") (pinfunction "INT_12") (pintype "passive"))
    )
    (net (code "68") (name "Net-(U2-REGOUT)") (class "Default")
      (node (ref "C4") (pin "2") (pintype "passive"))
      (node (ref "U2") (pin "10") (pinfunction "REGOUT_10") (pintype "passive"))
    )
    (net (code "69") (name "Net-(U4-BST)") (class "Default")
      (node (ref "C16") (pin "1") (pintype "passive"))
      (node (ref "U4") (pin "6") (pinfunction "BST_6") (pintype "passive"))
    )
    (net (code "70") (name "Net-(U4-FB)") (class "Default")
      (node (ref "R18") (pin "1") (pintype "passive"))
      (node (ref "R21") (pin "1") (pintype "passive"))
      (node (ref "R23") (pin "2") (pintype "passive"))
      (node (ref "U4") (pin "4") (pinfunction "FB_4") (pintype "passive"))
    )
    (net (code "71") (name "Net-(U4-SW)") (class "Default")
      (node (ref "C16") (pin "2") (pintype "passive"))
      (node (ref "L1") (pin "1") (pinfunction "1_1") (pintype "passive"))
      (node (ref "U4") (pin "2") (pinfunction "SW_2") (pintype "passive"))
    )
    (net (code "72") (name "unconnected-(CON4-CC1-PadB5)") (class "Default")
      (node (ref "CON4") (pin "B5") (pinfunction "CC1_B5") (pintype "passive"))
    )
    (net (code "73") (name "unconnected-(CON4-RX2+-PadA11)") (class "Default")
      (node (ref "CON4") (pin "A11") (pinfunction "RX2+_A11") (pintype "passive"))
    )
    (net (code "74") (name "unconnected-(CON4-RX2+-PadB11)") (class "Default")
      (node (ref "CON4") (pin "B11") (pinfunction "RX2+_B11") (pintype "passive"))
    )
    (net (code "75") (name "unconnected-(CON4-RX2--PadA10)") (class "Default")
      (node (ref "CON4") (pin "A10") (pinfunction "RX2-_A10") (pintype "passive"))
    )
    (net (code "76") (name "unconnected-(CON4-RX2--PadB10)") (class "Default")
      (node (ref "CON4") (pin "B10") (pinfunction "RX2-_B10") (pintype "passive"))
    )
    (net (code "77") (name "unconnected-(CON4-SBU1-PadA8)") (class "Default")
      (node (ref "CON4") (pin "A8") (pinfunction "SBU1_A8") (pintype "passive"))
    )
    (net (code "78") (name "unconnected-(CON4-SBU1-PadB8)") (class "Default")
      (node (ref "CON4") (pin "B8") (pinfunction "SBU1_B8") (pintype "passive"))
    )
    (net (code "79") (name "unconnected-(CON4-TX1+-PadA2)") (class "Default")
      (node (ref "CON4") (pin "A2") (pinfunction "TX1+_A2") (pintype "passive"))
    )
    (net (code "80") (name "unconnected-(CON4-TX1+-PadB2)") (class "Default")
      (node (ref "CON4") (pin "B2") (pinfunction "TX1+_B2") (pintype "passive"))
    )
    (net (code "81") (name "unconnected-(CON4-TX1--PadA3)") (class "Default")
      (node (ref "CON4") (pin "A3") (pinfunction "TX1-_A3") (pintype "passive"))
    )
    (net (code "82") (name "unconnected-(CON4-TX1--PadB3)") (class "Default")
      (node (ref "CON4") (pin "B3") (pinfunction "TX1-_B3") (pintype "passive"))
    )
    (net (code "83") (name "unconnected-(I.MX1-1-PadJ1_1)") (class "Default")
      (node (ref "I.MX1") (pin "J1_1") (pinfunction "1_J1_1") (pintype "passive"))
    )
    (net (code "84") (name "unconnected-(I.MX1-2-PadJ1_2)") (class "Default")
      (node (ref "I.MX1") (pin "J1_2") (pinfunction "2_J1_2") (pintype "passive"))
    )
    (net (code "85") (name "unconnected-(I.MX1-3-PadJ1_3)") (class "Default")
      (node (ref "I.MX1") (pin "J1_3") (pinfunction "3_J1_3") (pintype "passive"))
    )
    (net (code "86") (name "unconnected-(I.MX1-3-PadJ2_3)") (class "Default")
      (node (ref "I.MX1") (pin "J2_3") (pinfunction "3_J2_3") (pintype "passive"))
    )
    (net (code "87") (name "unconnected-(I.MX1-4-PadJ1_4)") (class "Default")
      (node (ref "I.MX1") (pin "J1_4") (pinfunction "4_J1_4") (pintype "passive"))
    )
    (net (code "88") (name "unconnected-(I.MX1-4-PadJ2_4)") (class "Default")
      (node (ref "I.MX1") (pin "J2_4") (pinfunction "4_J2_4") (pintype "passive"))
    )
    (net (code "89") (name "unconnected-(I.MX1-5-PadJ1_5)") (class "Default")
      (node (ref "I.MX1") (pin "J1_5") (pinfunction "5_J1_5") (pintype "passive"))
    )
    (net (code "90") (name "unconnected-(I.MX1-5-PadJ2_5)") (class "Default")
      (node (ref "I.MX1") (pin "J2_5") (pinfunction "5_J2_5") (pintype "passive"))
    )
    (net (code "91") (name "unconnected-(I.MX1-6-PadJ1_6)") (class "Default")
      (node (ref "I.MX1") (pin "J1_6") (pinfunction "6_J1_6") (pintype "passive"))
    )
    (net (code "92") (name "unconnected-(I.MX1-6-PadJ2_6)") (class "Default")
      (node (ref "I.MX1") (pin "J2_6") (pinfunction "6_J2_6") (pintype "passive"))
    )
    (net (code "93") (name "unconnected-(I.MX1-7-PadJ1_7)") (class "Default")
      (node (ref "I.MX1") (pin "J1_7") (pinfunction "7_J1_7") (pintype "passive"))
    )
    (net (code "94") (name "unconnected-(I.MX1-7-PadJ2_7)") (class "Default")
      (node (ref "I.MX1") (pin "J2_7") (pinfunction "7_J2_7") (pintype "passive"))
    )
    (net (code "95") (name "unconnected-(I.MX1-8-PadJ1_8)") (class "Default")
      (node (ref "I.MX1") (pin "J1_8") (pinfunction "8_J1_8") (pintype "passive"))
    )
    (net (code "96") (name "unconnected-(I.MX1-8-PadJ2_8)") (class "Default")
      (node (ref "I.MX1") (pin "J2_8") (pinfunction "8_J2_8") (pintype "passive"))
    )
    (net (code "97") (name "unconnected-(I.MX1-9-PadJ1_9)") (class "Default")
      (node (ref "I.MX1") (pin "J1_9") (pinfunction "9_J1_9") (pintype "passive"))
    )
    (net (code "98") (name "unconnected-(I.MX1-9-PadJ2_9)") (class "Default")
      (node (ref "I.MX1") (pin "J2_9") (pinfunction "9_J2_9") (pintype "passive"))
    )
    (net (code "99") (name "unconnected-(I.MX1-10-PadJ1_10)") (class "Default")
      (node (ref "I.MX1") (pin "J1_10") (pinfunction "10_J1_10") (pintype "passive"))
    )
    (net (code "100") (name "unconnected-(I.MX1-10-PadJ2_10)") (class "Default")
      (node (ref "I.MX1") (pin "J2_10") (pinfunction "10_J2_10") (pintype "passive"))
    )
    (net (code "101") (name "unconnected-(I.MX1-11-PadJ1_11)") (class "Default")
      (node (ref "I.MX1") (pin "J1_11") (pinfunction "11_J1_11") (pintype "passive"))
    )
    (net (code "102") (name "unconnected-(I.MX1-11-PadJ2_11)") (class "Default")
      (node (ref "I.MX1") (pin "J2_11") (pinfunction "11_J2_11") (pintype "passive"))
    )
    (net (code "103") (name "unconnected-(I.MX1-12-PadJ1_12)") (class "Default")
      (node (ref "I.MX1") (pin "J1_12") (pinfunction "12_J1_12") (pintype "passive"))
    )
    (net (code "104") (name "unconnected-(I.MX1-12-PadJ2_12)") (class "Default")
      (node (ref "I.MX1") (pin "J2_12") (pinfunction "12_J2_12") (pintype "passive"))
    )
    (net (code "105") (name "unconnected-(I.MX1-13-PadJ1_13)") (class "Default")
      (node (ref "I.MX1") (pin "J1_13") (pinfunction "13_J1_13") (pintype "passive"))
    )
    (net (code "106") (name "unconnected-(I.MX1-13-PadJ2_13)") (class "Default")
      (node (ref "I.MX1") (pin "J2_13") (pinfunction "13_J2_13") (pintype "passive"))
    )
    (net (code "107") (name "unconnected-(I.MX1-14-PadJ1_14)") (class "Default")
      (node (ref "I.MX1") (pin "J1_14") (pinfunction "14_J1_14") (pintype "passive"))
    )
    (net (code "108") (name "unconnected-(I.MX1-14-PadJ2_14)") (class "Default")
      (node (ref "I.MX1") (pin "J2_14") (pinfunction "14_J2_14") (pintype "passive"))
    )
    (net (code "109") (name "unconnected-(I.MX1-15-PadJ1_15)") (class "Default")
      (node (ref "I.MX1") (pin "J1_15") (pinfunction "15_J1_15") (pintype "passive"))
    )
    (net (code "110") (name "unconnected-(I.MX1-15-PadJ2_15)") (class "Default")
      (node (ref "I.MX1") (pin "J2_15") (pinfunction "15_J2_15") (pintype "passive"))
    )
    (net (code "111") (name "unconnected-(I.MX1-16-PadJ1_16)") (class "Default")
      (node (ref "I.MX1") (pin "J1_16") (pinfunction "16_J1_16") (pintype "passive"))
    )
    (net (code "112") (name "unconnected-(I.MX1-17-PadJ1_17)") (class "Default")
      (node (ref "I.MX1") (pin "J1_17") (pinfunction "17_J1_17") (pintype "passive"))
    )
    (net (code "113") (name "unconnected-(I.MX1-18-PadJ1_18)") (class "Default")
      (node (ref "I.MX1") (pin "J1_18") (pinfunction "18_J1_18") (pintype "passive"))
    )
    (net (code "114") (name "unconnected-(I.MX1-19-PadJ1_19)") (class "Default")
      (node (ref "I.MX1") (pin "J1_19") (pinfunction "19_J1_19") (pintype "passive"))
    )
    (net (code "115") (name "unconnected-(I.MX1-20-PadJ1_20)") (class "Default")
      (node (ref "I.MX1") (pin "J1_20") (pinfunction "20_J1_20") (pintype "passive"))
    )
    (net (code "116") (name "unconnected-(I.MX1-21-PadJ1_21)") (class "Default")
      (node (ref "I.MX1") (pin "J1_21") (pinfunction "21_J1_21") (pintype "passive"))
    )
    (net (code "117") (name "unconnected-(I.MX1-22-PadJ1_22)") (class "Default")
      (node (ref "I.MX1") (pin "J1_22") (pinfunction "22_J1_22") (pintype "passive"))
    )
    (net (code "118") (name "unconnected-(I.MX1-22-PadJ2_22)") (class "Default")
      (node (ref "I.MX1") (pin "J2_22") (pinfunction "22_J2_22") (pintype "passive"))
    )
    (net (code "119") (name "unconnected-(I.MX1-23-PadJ1_23)") (class "Default")
      (node (ref "I.MX1") (pin "J1_23") (pinfunction "23_J1_23") (pintype "passive"))
    )
    (net (code "120") (name "unconnected-(I.MX1-23-PadJ2_23)") (class "Default")
      (node (ref "I.MX1") (pin "J2_23") (pinfunction "23_J2_23") (pintype "passive"))
    )
    (net (code "121") (name "unconnected-(I.MX1-24-PadJ1_24)") (class "Default")
      (node (ref "I.MX1") (pin "J1_24") (pinfunction "24_J1_24") (pintype "passive"))
    )
    (net (code "122") (name "unconnected-(I.MX1-24-PadJ2_24)") (class "Default")
      (node (ref "I.MX1") (pin "J2_24") (pinfunction "24_J2_24") (pintype "passive"))
    )
    (net (code "123") (name "unconnected-(I.MX1-25-PadJ1_25)") (class "Default")
      (node (ref "I.MX1") (pin "J1_25") (pinfunction "25_J1_25") (pintype "passive"))
    )
    (net (code "124") (name "unconnected-(I.MX1-25-PadJ2_25)") (class "Default")
      (node (ref "I.MX1") (pin "J2_25") (pinfunction "25_J2_25") (pintype "passive"))
    )
    (net (code "125") (name "unconnected-(I.MX1-26-PadJ1_26)") (class "Default")
      (node (ref "I.MX1") (pin "J1_26") (pinfunction "26_J1_26") (pintype "passive"))
    )
    (net (code "126") (name "unconnected-(I.MX1-26-PadJ2_26)") (class "Default")
      (node (ref "I.MX1") (pin "J2_26") (pinfunction "26_J2_26") (pintype "passive"))
    )
    (net (code "127") (name "unconnected-(I.MX1-27-PadJ1_27)") (class "Default")
      (node (ref "I.MX1") (pin "J1_27") (pinfunction "27_J1_27") (pintype "passive"))
    )
    (net (code "128") (name "unconnected-(I.MX1-27-PadJ2_27)") (class "Default")
      (node (ref "I.MX1") (pin "J2_27") (pinfunction "27_J2_27") (pintype "passive"))
    )
    (net (code "129") (name "unconnected-(I.MX1-28-PadJ1_28)") (class "Default")
      (node (ref "I.MX1") (pin "J1_28") (pinfunction "28_J1_28") (pintype "passive"))
    )
    (net (code "130") (name "unconnected-(I.MX1-28-PadJ2_28)") (class "Default")
      (node (ref "I.MX1") (pin "J2_28") (pinfunction "28_J2_28") (pintype "passive"))
    )
    (net (code "131") (name "unconnected-(I.MX1-29-PadJ1_29)") (class "Default")
      (node (ref "I.MX1") (pin "J1_29") (pinfunction "29_J1_29") (pintype "passive"))
    )
    (net (code "132") (name "unconnected-(I.MX1-29-PadJ2_29)") (class "Default")
      (node (ref "I.MX1") (pin "J2_29") (pinfunction "29_J2_29") (pintype "passive"))
    )
    (net (code "133") (name "unconnected-(I.MX1-30-PadJ1_30)") (class "Default")
      (node (ref "I.MX1") (pin "J1_30") (pinfunction "30_J1_30") (pintype "passive"))
    )
    (net (code "134") (name "unconnected-(I.MX1-30-PadJ2_30)") (class "Default")
      (node (ref "I.MX1") (pin "J2_30") (pinfunction "30_J2_30") (pintype "passive"))
    )
    (net (code "135") (name "unconnected-(I.MX1-31-PadJ1_31)") (class "Default")
      (node (ref "I.MX1") (pin "J1_31") (pinfunction "31_J1_31") (pintype "passive"))
    )
    (net (code "136") (name "unconnected-(I.MX1-32-PadJ1_32)") (class "Default")
      (node (ref "I.MX1") (pin "J1_32") (pinfunction "32_J1_32") (pintype "passive"))
    )
    (net (code "137") (name "unconnected-(I.MX1-33-PadJ1_33)") (class "Default")
      (node (ref "I.MX1") (pin "J1_33") (pinfunction "33_J1_33") (pintype "passive"))
    )
    (net (code "138") (name "unconnected-(I.MX1-34-PadJ1_34)") (class "Default")
      (node (ref "I.MX1") (pin "J1_34") (pinfunction "34_J1_34") (pintype "passive"))
    )
    (net (code "139") (name "unconnected-(I.MX1-35-PadJ1_35)") (class "Default")
      (node (ref "I.MX1") (pin "J1_35") (pinfunction "35_J1_35") (pintype "passive"))
    )
    (net (code "140") (name "unconnected-(I.MX1-36-PadJ1_36)") (class "Default")
      (node (ref "I.MX1") (pin "J1_36") (pinfunction "36_J1_36") (pintype "passive"))
    )
    (net (code "141") (name "unconnected-(I.MX1-37-PadJ1_37)") (class "Default")
      (node (ref "I.MX1") (pin "J1_37") (pinfunction "37_J1_37") (pintype "passive"))
    )
    (net (code "142") (name "unconnected-(I.MX1-38-PadJ1_38)") (class "Default")
      (node (ref "I.MX1") (pin "J1_38") (pinfunction "38_J1_38") (pintype "passive"))
    )
    (net (code "143") (name "unconnected-(I.MX1-39-PadJ1_39)") (class "Default")
      (node (ref "I.MX1") (pin "J1_39") (pinfunction "39_J1_39") (pintype "passive"))
    )
    (net (code "144") (name "unconnected-(I.MX1-42-PadJ1_42)") (class "Default")
      (node (ref "I.MX1") (pin "J1_42") (pinfunction "42_J1_42") (pintype "passive"))
    )
    (net (code "145") (name "unconnected-(I.MX1-43-PadJ1_43)") (class "Default")
      (node (ref "I.MX1") (pin "J1_43") (pinfunction "43_J1_43") (pintype "passive"))
    )
    (net (code "146") (name "unconnected-(I.MX1-44-PadJ1_44)") (class "Default")
      (node (ref "I.MX1") (pin "J1_44") (pinfunction "44_J1_44") (pintype "passive"))
    )
    (net (code "147") (name "unconnected-(I.MX1-45-PadJ1_45)") (class "Default")
      (node (ref "I.MX1") (pin "J1_45") (pinfunction "45_J1_45") (pintype "passive"))
    )
    (net (code "148") (name "unconnected-(I.MX1-46-PadJ1_46)") (class "Default")
      (node (ref "I.MX1") (pin "J1_46") (pinfunction "46_J1_46") (pintype "passive"))
    )
    (net (code "149") (name "unconnected-(I.MX1-47-PadJ1_47)") (class "Default")
      (node (ref "I.MX1") (pin "J1_47") (pinfunction "47_J1_47") (pintype "passive"))
    )
    (net (code "150") (name "unconnected-(I.MX1-47-PadJ2_47)") (class "Default")
      (node (ref "I.MX1") (pin "J2_47") (pinfunction "47_J2_47") (pintype "passive"))
    )
    (net (code "151") (name "unconnected-(I.MX1-52-PadJ2_52)") (class "Default")
      (node (ref "I.MX1") (pin "J2_52") (pinfunction "52_J2_52") (pintype "passive"))
    )
    (net (code "152") (name "unconnected-(I.MX1-55-PadJ1_55)") (class "Default")
      (node (ref "I.MX1") (pin "J1_55") (pinfunction "55_J1_55") (pintype "passive"))
    )
    (net (code "153") (name "unconnected-(I.MX1-56-PadJ1_56)") (class "Default")
      (node (ref "I.MX1") (pin "J1_56") (pinfunction "56_J1_56") (pintype "passive"))
    )
    (net (code "154") (name "unconnected-(I.MX1-57-PadJ1_57)") (class "Default")
      (node (ref "I.MX1") (pin "J1_57") (pinfunction "57_J1_57") (pintype "passive"))
    )
    (net (code "155") (name "unconnected-(I.MX1-58-PadJ1_58)") (class "Default")
      (node (ref "I.MX1") (pin "J1_58") (pinfunction "58_J1_58") (pintype "passive"))
    )
    (net (code "156") (name "unconnected-(I.MX1-59-PadJ1_59)") (class "Default")
      (node (ref "I.MX1") (pin "J1_59") (pinfunction "59_J1_59") (pintype "passive"))
    )
    (net (code "157") (name "unconnected-(I.MX1-60-PadJ1_60)") (class "Default")
      (node (ref "I.MX1") (pin "J1_60") (pinfunction "60_J1_60") (pintype "passive"))
    )
    (net (code "158") (name "unconnected-(U1-AUXL-Pad19)") (class "Default")
      (node (ref "U1") (pin "19") (pinfunction "AUXL_19") (pintype "passive"))
    )
    (net (code "159") (name "unconnected-(U1-AUXR-Pad20)") (class "Default")
      (node (ref "U1") (pin "20") (pinfunction "AUXR_20") (pintype "passive"))
    )
    (net (code "160") (name "unconnected-(U1-CSB{slash}GPIO1-Pad15)") (class "Default")
      (node (ref "U1") (pin "15") (pinfunction "CSB/GPIO1_15") (pintype "passive"))
    )
    (net (code "161") (name "unconnected-(U1-L2{slash}GPIO2-Pad3)") (class "Default")
      (node (ref "U1") (pin "3") (pinfunction "L2/GPIO2_3") (pintype "passive"))
    )
    (net (code "162") (name "unconnected-(U1-LOUT1-Pad30)") (class "Default")
      (node (ref "U1") (pin "30") (pinfunction "LOUT1_30") (pintype "passive"))
    )
    (net (code "163") (name "unconnected-(U1-OUT3-Pad22)") (class "Default")
      (node (ref "U1") (pin "22") (pinfunction "OUT3_22") (pintype "passive"))
    )
    (net (code "164") (name "unconnected-(U1-OUT4-Pad21)") (class "Default")
      (node (ref "U1") (pin "21") (pinfunction "OUT4_21") (pintype "passive"))
    )
    (net (code "165") (name "unconnected-(U1-R2{slash}GPIO3-Pad6)") (class "Default")
      (node (ref "U1") (pin "6") (pinfunction "R2/GPIO3_6") (pintype "passive"))
    )
    (net (code "166") (name "unconnected-(U1-ROUT1-Pad29)") (class "Default")
      (node (ref "U1") (pin "29") (pinfunction "ROUT1_29") (pintype "passive"))
    )
    (net (code "167") (name "unconnected-(U2-AUX_CL-Pad7)") (class "Default")
      (node (ref "U2") (pin "7") (pinfunction "AUX_CL_7") (pintype "passive"))
    )
    (net (code "168") (name "unconnected-(U2-AUX_DA-Pad6)") (class "Default")
      (node (ref "U2") (pin "6") (pinfunction "AUX_DA_6") (pintype "passive"))
    )
    (net (code "169") (name "unconnected-(U2-NC-Pad2)") (class "Default")
      (node (ref "U2") (pin "2") (pinfunction "NC_2") (pintype "passive"))
    )
    (net (code "170") (name "unconnected-(U2-NC-Pad3)") (class "Default")
      (node (ref "U2") (pin "3") (pinfunction "NC_3") (pintype "passive"))
    )
    (net (code "171") (name "unconnected-(U2-NC-Pad4)") (class "Default")
      (node (ref "U2") (pin "4") (pinfunction "NC_4") (pintype "passive"))
    )
    (net (code "172") (name "unconnected-(U2-NC-Pad5)") (class "Default")
      (node (ref "U2") (pin "5") (pinfunction "NC_5") (pintype "passive"))
    )
    (net (code "173") (name "unconnected-(U2-NC-Pad14)") (class "Default")
      (node (ref "U2") (pin "14") (pinfunction "NC_14") (pintype "passive"))
    )
    (net (code "174") (name "unconnected-(U2-NC-Pad15)") (class "Default")
      (node (ref "U2") (pin "15") (pinfunction "NC_15") (pintype "passive"))
    )
    (net (code "175") (name "unconnected-(U2-NC-Pad16)") (class "Default")
      (node (ref "U2") (pin "16") (pinfunction "NC_16") (pintype "passive"))
    )
    (net (code "176") (name "unconnected-(U2-NC-Pad17)") (class "Default")
      (node (ref "U2") (pin "17") (pinfunction "NC_17") (pintype "passive"))
    )
    (net (code "177") (name "unconnected-(U2-RESV-Pad19)") (class "Default")
      (node (ref "U2") (pin "19") (pinfunction "RESV_19") (pintype "passive"))
    )
    (net (code "178") (name "unconnected-(U2-RESV-Pad21)") (class "Default")
      (node (ref "U2") (pin "21") (pinfunction "RESV_21") (pintype "passive"))
    )
    (net (code "179") (name "unconnected-(U2-RESV-Pad22)") (class "Default")
      (node (ref "U2") (pin "22") (pinfunction "RESV_22") (pintype "passive"))
    )
    (net (code "180") (name "unconnected-(U3-CTS#-Pad9)") (class "Default")
      (node (ref "U3") (pin "9") (pinfunction "CTS#_9") (pintype "passive"))
    )
    (net (code "181") (name "unconnected-(U3-DCD#-Pad12)") (class "Default")
      (node (ref "U3") (pin "12") (pinfunction "DCD#_12") (pintype "passive"))
    )
    (net (code "182") (name "unconnected-(U3-DSR#-Pad10)") (class "Default")
      (node (ref "U3") (pin "10") (pinfunction "DSR#_10") (pintype "passive"))
    )
    (net (code "183") (name "unconnected-(U3-DTR#-Pad13)") (class "Default")
      (node (ref "U3") (pin "13") (pinfunction "DTR#_13") (pintype "passive"))
    )
    (net (code "184") (name "unconnected-(U3-R232-Pad15)") (class "Default")
      (node (ref "U3") (pin "15") (pinfunction "R232_15") (pintype "passive"))
    )
    (net (code "185") (name "unconnected-(U3-RI#-Pad11)") (class "Default")
      (node (ref "U3") (pin "11") (pinfunction "RI#_11") (pintype "passive"))
    )
    (net (code "186") (name "unconnected-(U3-RTS#-Pad14)") (class "Default")
      (node (ref "U3") (pin "14") (pinfunction "RTS#_14") (pintype "passive"))
    )
    (net (code "187") (name "unconnected-(U3-XI-Pad7)") (class "Default")
      (node (ref "U3") (pin "7") (pinfunction "XI_7") (pintype "passive"))
    )
    (net (code "188") (name "unconnected-(U3-XO-Pad8)") (class "Default")
      (node (ref "U3") (pin "8") (pinfunction "XO_8") (pintype "passive"))
    )
  )
)
